# bldc_driver.net
KiCad netlist of a schematic drawn in EasyEDA Pro
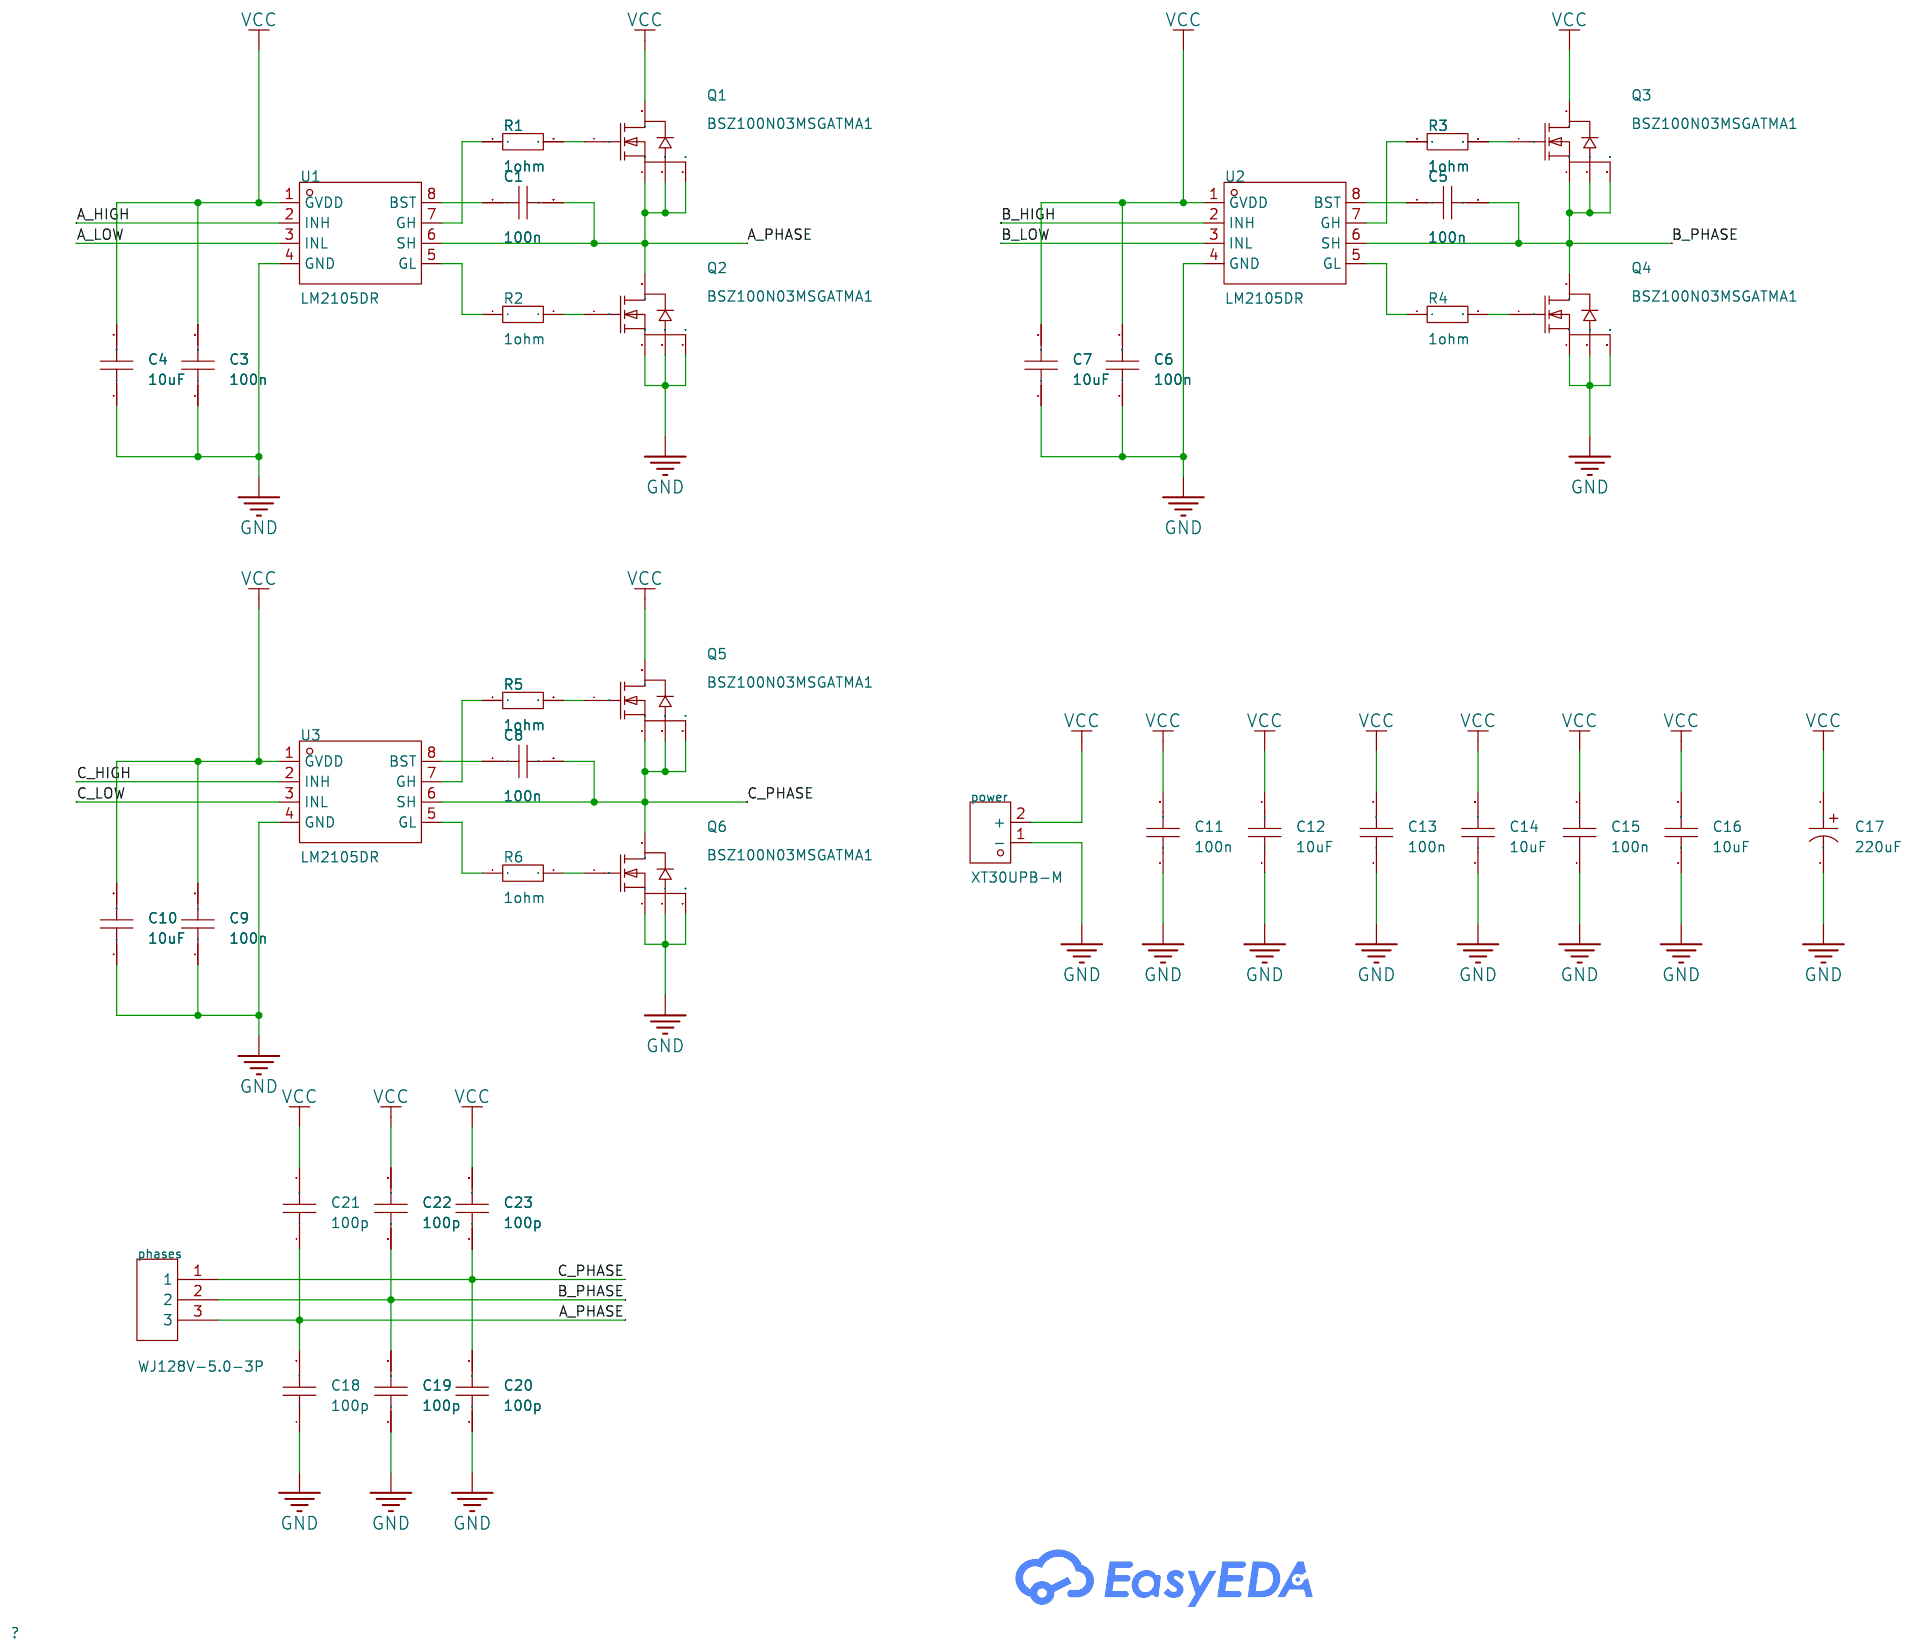
[diagram p0: power_drivers]
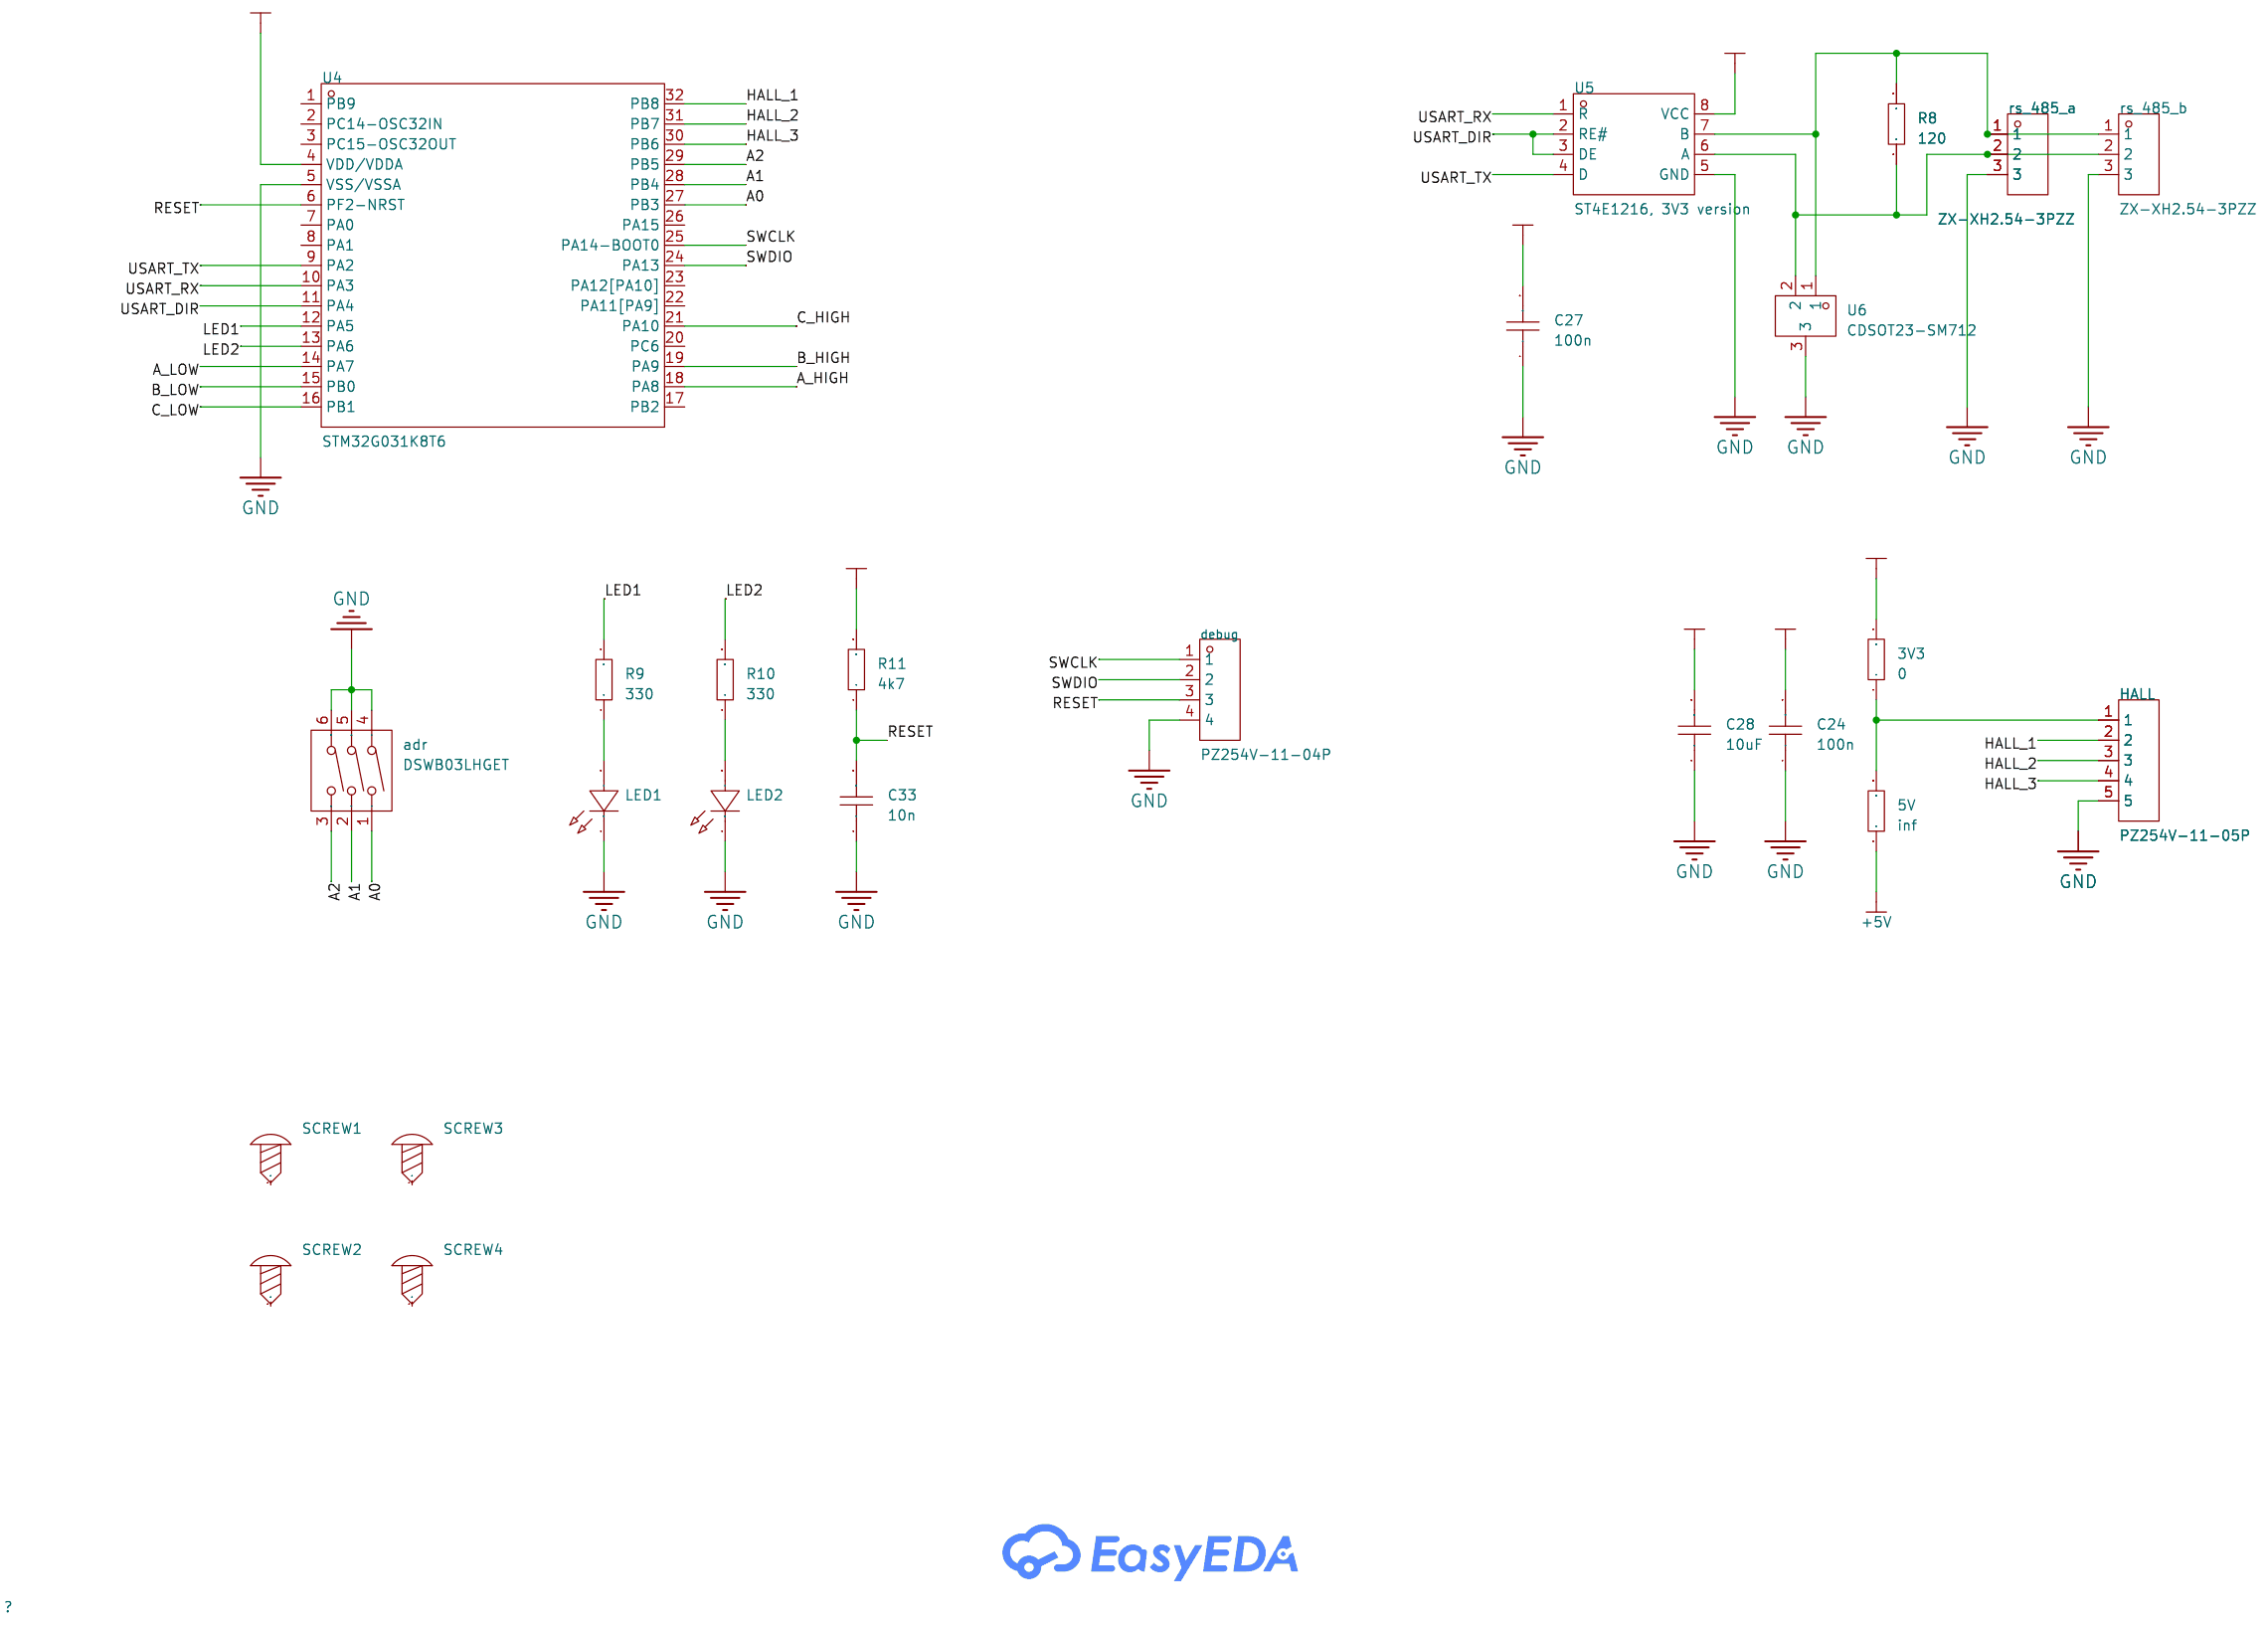
[diagram p1: main]
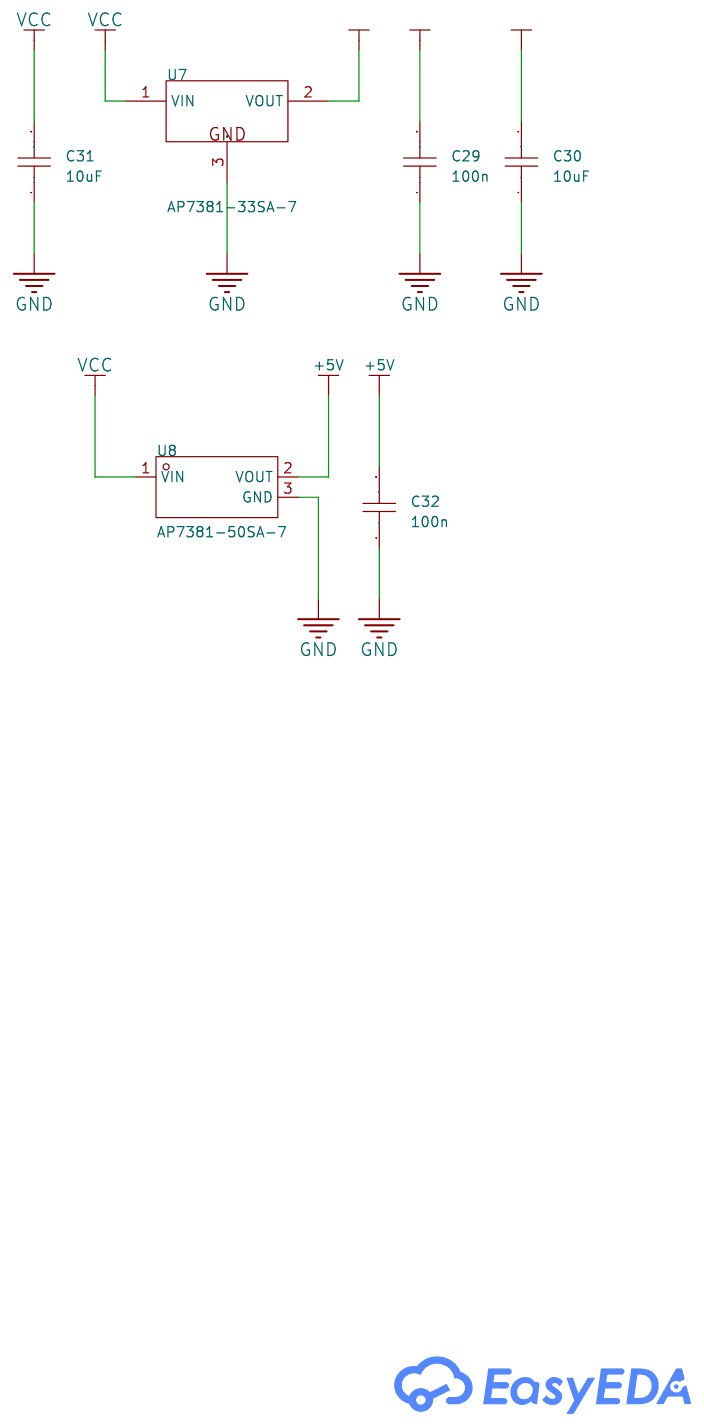
[diagram p2: supply]

(export (version "E")
  (design (tool "Eeschema 10.0.6"))
  (components
    (comp (ref "C1")
      (value "10uF")
      (footprint "easyedapro:C0805")
      (description "Capacitance:10uF Tolerance:±10% Tolerance:±10% Voltage Rating:25V Temperature Coefficient:X5R")
      (fields
        (field (name "Manufacturer Part") "CL21A106KAYNNNE")
        (field (name "Manufacturer") "SAMSUNG(三星)")
      )
      (libsource (lib "easyedapro") (part "CL21A106KAYNNNE"))
    )
    (comp (ref "C3")
      (value "10uF")
      (footprint "easyedapro:C0805")
      (description "Capacitance:10uF Tolerance:±10% Tolerance:±10% Voltage Rating:25V Temperature Coefficient:X5R")
      (fields
        (field (name "Manufacturer Part") "CL21A106KAYNNNE")
        (field (name "Manufacturer") "SAMSUNG(三星)")
      )
      (libsource (lib "easyedapro") (part "CL21A106KAYNNNE"))
    )
    (comp (ref "C4")
      (value "10uF")
      (footprint "easyedapro:C0805")
      (description "Capacitance:10uF Tolerance:±10% Tolerance:±10% Voltage Rating:25V Temperature Coefficient:X5R")
      (fields
        (field (name "Manufacturer Part") "CL21A106KAYNNNE")
        (field (name "Manufacturer") "SAMSUNG(三星)")
      )
      (libsource (lib "easyedapro") (part "CL21A106KAYNNNE"))
    )
    (comp (ref "C5")
      (value "10uF")
      (footprint "easyedapro:C0805")
      (description "Capacitance:10uF Tolerance:±10% Tolerance:±10% Voltage Rating:25V Temperature Coefficient:X5R")
      (fields
        (field (name "Manufacturer Part") "CL21A106KAYNNNE")
        (field (name "Manufacturer") "SAMSUNG(三星)")
      )
      (libsource (lib "easyedapro") (part "CL21A106KAYNNNE"))
    )
    (comp (ref "C6")
      (value "10uF")
      (footprint "easyedapro:C0805")
      (description "Capacitance:10uF Tolerance:±10% Tolerance:±10% Voltage Rating:25V Temperature Coefficient:X5R")
      (fields
        (field (name "Manufacturer Part") "CL21A106KAYNNNE")
        (field (name "Manufacturer") "SAMSUNG(三星)")
      )
      (libsource (lib "easyedapro") (part "CL21A106KAYNNNE"))
    )
    (comp (ref "C7")
      (value "10uF")
      (footprint "easyedapro:C0805")
      (description "Capacitance:10uF Tolerance:±10% Tolerance:±10% Voltage Rating:25V Temperature Coefficient:X5R")
      (fields
        (field (name "Manufacturer Part") "CL21A106KAYNNNE")
        (field (name "Manufacturer") "SAMSUNG(三星)")
      )
      (libsource (lib "easyedapro") (part "CL21A106KAYNNNE"))
    )
    (comp (ref "C8")
      (value "10uF")
      (footprint "easyedapro:C0805")
      (description "Capacitance:10uF Tolerance:±10% Tolerance:±10% Voltage Rating:25V Temperature Coefficient:X5R")
      (fields
        (field (name "Manufacturer Part") "CL21A106KAYNNNE")
        (field (name "Manufacturer") "SAMSUNG(三星)")
      )
      (libsource (lib "easyedapro") (part "CL21A106KAYNNNE"))
    )
    (comp (ref "C9")
      (value "10uF")
      (footprint "easyedapro:C0805")
      (description "Capacitance:10uF Tolerance:±10% Tolerance:±10% Voltage Rating:25V Temperature Coefficient:X5R")
      (fields
        (field (name "Manufacturer Part") "CL21A106KAYNNNE")
        (field (name "Manufacturer") "SAMSUNG(三星)")
      )
      (libsource (lib "easyedapro") (part "CL21A106KAYNNNE"))
    )
    (comp (ref "C10")
      (value "10uF")
      (footprint "easyedapro:C0805")
      (description "Capacitance:10uF Tolerance:±10% Tolerance:±10% Voltage Rating:25V Temperature Coefficient:X5R")
      (fields
        (field (name "Manufacturer Part") "CL21A106KAYNNNE")
        (field (name "Manufacturer") "SAMSUNG(三星)")
      )
      (libsource (lib "easyedapro") (part "CL21A106KAYNNNE"))
    )
    (comp (ref "C11")
      (value "10uF")
      (footprint "easyedapro:C0805")
      (description "Capacitance:10uF Tolerance:±10% Tolerance:±10% Voltage Rating:25V Temperature Coefficient:X5R")
      (fields
        (field (name "Manufacturer Part") "CL21A106KAYNNNE")
        (field (name "Manufacturer") "SAMSUNG(三星)")
      )
      (libsource (lib "easyedapro") (part "CL21A106KAYNNNE"))
    )
    (comp (ref "C12")
      (value "10uF")
      (footprint "easyedapro:C0805")
      (description "Capacitance:10uF Tolerance:±10% Tolerance:±10% Voltage Rating:25V Temperature Coefficient:X5R")
      (fields
        (field (name "Manufacturer Part") "CL21A106KAYNNNE")
        (field (name "Manufacturer") "SAMSUNG(三星)")
      )
      (libsource (lib "easyedapro") (part "CL21A106KAYNNNE"))
    )
    (comp (ref "C13")
      (value "10uF")
      (footprint "easyedapro:C0805")
      (description "Capacitance:10uF Tolerance:±10% Tolerance:±10% Voltage Rating:25V Temperature Coefficient:X5R")
      (fields
        (field (name "Manufacturer Part") "CL21A106KAYNNNE")
        (field (name "Manufacturer") "SAMSUNG(三星)")
      )
      (libsource (lib "easyedapro") (part "CL21A106KAYNNNE"))
    )
    (comp (ref "C14")
      (value "10uF")
      (footprint "easyedapro:C0805")
      (description "Capacitance:10uF Tolerance:±10% Tolerance:±10% Voltage Rating:25V Temperature Coefficient:X5R")
      (fields
        (field (name "Manufacturer Part") "CL21A106KAYNNNE")
        (field (name "Manufacturer") "SAMSUNG(三星)")
      )
      (libsource (lib "easyedapro") (part "CL21A106KAYNNNE"))
    )
    (comp (ref "C15")
      (value "10uF")
      (footprint "easyedapro:C0805")
      (description "Capacitance:10uF Tolerance:±10% Tolerance:±10% Voltage Rating:25V Temperature Coefficient:X5R")
      (fields
        (field (name "Manufacturer Part") "CL21A106KAYNNNE")
        (field (name "Manufacturer") "SAMSUNG(三星)")
      )
      (libsource (lib "easyedapro") (part "CL21A106KAYNNNE"))
    )
    (comp (ref "C16")
      (value "10uF")
      (footprint "easyedapro:C0805")
      (description "Capacitance:10uF Tolerance:±10% Tolerance:±10% Voltage Rating:25V Temperature Coefficient:X5R")
      (fields
        (field (name "Manufacturer Part") "CL21A106KAYNNNE")
        (field (name "Manufacturer") "SAMSUNG(三星)")
      )
      (libsource (lib "easyedapro") (part "CL21A106KAYNNNE"))
    )
    (comp (ref "C17")
      (value "220uF")
      (footprint "easyedapro:CAP-SMD_BD10.0-L10.3-W10.3-LS10.9-FD")
      (fields (field (name "Manufacturer Part") "XT1E221M1010") (field (name "Manufacturer") "JARSON(伽盛)"))
      (libsource (lib "easyedapro") (part "XT1E221M1010"))
    )
    (comp (ref "C18")
      (value "10uF")
      (footprint "easyedapro:C0805")
      (description "Capacitance:10uF Tolerance:±10% Tolerance:±10% Voltage Rating:25V Temperature Coefficient:X5R")
      (fields
        (field (name "Manufacturer Part") "CL21A106KAYNNNE")
        (field (name "Manufacturer") "SAMSUNG(三星)")
      )
      (libsource (lib "easyedapro") (part "CL21A106KAYNNNE"))
    )
    (comp (ref "C19")
      (value "10uF")
      (footprint "easyedapro:C0805")
      (description "Capacitance:10uF Tolerance:±10% Tolerance:±10% Voltage Rating:25V Temperature Coefficient:X5R")
      (fields
        (field (name "Manufacturer Part") "CL21A106KAYNNNE")
        (field (name "Manufacturer") "SAMSUNG(三星)")
      )
      (libsource (lib "easyedapro") (part "CL21A106KAYNNNE"))
    )
    (comp (ref "C20")
      (value "10uF")
      (footprint "easyedapro:C0805")
      (description "Capacitance:10uF Tolerance:±10% Tolerance:±10% Voltage Rating:25V Temperature Coefficient:X5R")
      (fields
        (field (name "Manufacturer Part") "CL21A106KAYNNNE")
        (field (name "Manufacturer") "SAMSUNG(三星)")
      )
      (libsource (lib "easyedapro") (part "CL21A106KAYNNNE"))
    )
    (comp (ref "C21")
      (value "10uF")
      (footprint "easyedapro:C0805")
      (description "Capacitance:10uF Tolerance:±10% Tolerance:±10% Voltage Rating:25V Temperature Coefficient:X5R")
      (fields
        (field (name "Manufacturer Part") "CL21A106KAYNNNE")
        (field (name "Manufacturer") "SAMSUNG(三星)")
      )
      (libsource (lib "easyedapro") (part "CL21A106KAYNNNE"))
    )
    (comp (ref "C22")
      (value "10uF")
      (footprint "easyedapro:C0805")
      (description "Capacitance:10uF Tolerance:±10% Tolerance:±10% Voltage Rating:25V Temperature Coefficient:X5R")
      (fields
        (field (name "Manufacturer Part") "CL21A106KAYNNNE")
        (field (name "Manufacturer") "SAMSUNG(三星)")
      )
      (libsource (lib "easyedapro") (part "CL21A106KAYNNNE"))
    )
    (comp (ref "C23")
      (value "10uF")
      (footprint "easyedapro:C0805")
      (description "Capacitance:10uF Tolerance:±10% Tolerance:±10% Voltage Rating:25V Temperature Coefficient:X5R")
      (fields
        (field (name "Manufacturer Part") "CL21A106KAYNNNE")
        (field (name "Manufacturer") "SAMSUNG(三星)")
      )
      (libsource (lib "easyedapro") (part "CL21A106KAYNNNE"))
    )
    (comp (ref "phases")
      (value "WJ128V-5.0-3P")
      (footprint "easyedapro:CONN-TH_3P-P5.00_WJ128V-5.0-3P")
      (fields (field (name "Manufacturer") "KANGNEX(康奈克斯电气)"))
      (libsource (lib "easyedapro") (part "WJ128V-5.0-3P"))
    )
    (comp (ref "power")
      (value "XT30UPB-M")
      (footprint "easyedapro:CONN-TH_XT30UPB-M")
      (fields (field (name "Manufacturer") "AMASS(艾迈斯)"))
      (libsource (lib "easyedapro") (part "XT30UPB-M"))
    )
    (comp (ref "Q1")
      (value "BSZ100N03MSGATMA1")
      (footprint "easyedapro:DFN-8_L3.3-W3.3-P0.65-BL-2")
      (fields (field (name "Manufacturer") "Infineon(英飞凌)"))
      (libsource (lib "easyedapro") (part "BSZ100N03MSGATMA1"))
    )
    (comp (ref "Q2")
      (value "BSZ100N03MSGATMA1")
      (footprint "easyedapro:DFN-8_L3.3-W3.3-P0.65-BL-2")
      (fields (field (name "Manufacturer") "Infineon(英飞凌)"))
      (libsource (lib "easyedapro") (part "BSZ100N03MSGATMA1"))
    )
    (comp (ref "Q3")
      (value "BSZ100N03MSGATMA1")
      (footprint "easyedapro:DFN-8_L3.3-W3.3-P0.65-BL-2")
      (fields (field (name "Manufacturer") "Infineon(英飞凌)"))
      (libsource (lib "easyedapro") (part "BSZ100N03MSGATMA1"))
    )
    (comp (ref "Q4")
      (value "BSZ100N03MSGATMA1")
      (footprint "easyedapro:DFN-8_L3.3-W3.3-P0.65-BL-2")
      (fields (field (name "Manufacturer") "Infineon(英飞凌)"))
      (libsource (lib "easyedapro") (part "BSZ100N03MSGATMA1"))
    )
    (comp (ref "Q5")
      (value "BSZ100N03MSGATMA1")
      (footprint "easyedapro:DFN-8_L3.3-W3.3-P0.65-BL-2")
      (fields (field (name "Manufacturer") "Infineon(英飞凌)"))
      (libsource (lib "easyedapro") (part "BSZ100N03MSGATMA1"))
    )
    (comp (ref "Q6")
      (value "BSZ100N03MSGATMA1")
      (footprint "easyedapro:DFN-8_L3.3-W3.3-P0.65-BL-2")
      (fields (field (name "Manufacturer") "Infineon(英飞凌)"))
      (libsource (lib "easyedapro") (part "BSZ100N03MSGATMA1"))
    )
    (comp (ref "R1")
      (value "10kΩ")
      (footprint "easyedapro:R0805")
      (fields
        (field (name "Manufacturer Part") "0805W8F1002T5E")
        (field (name "Manufacturer") "UNI-ROYAL(厚声)")
      )
      (libsource (lib "easyedapro") (part "0805W8F1002T5E"))
    )
    (comp (ref "R2")
      (value "10kΩ")
      (footprint "easyedapro:R0805")
      (fields
        (field (name "Manufacturer Part") "0805W8F1002T5E")
        (field (name "Manufacturer") "UNI-ROYAL(厚声)")
      )
      (libsource (lib "easyedapro") (part "0805W8F1002T5E"))
    )
    (comp (ref "R3")
      (value "10kΩ")
      (footprint "easyedapro:R0805")
      (fields
        (field (name "Manufacturer Part") "0805W8F1002T5E")
        (field (name "Manufacturer") "UNI-ROYAL(厚声)")
      )
      (libsource (lib "easyedapro") (part "0805W8F1002T5E"))
    )
    (comp (ref "R4")
      (value "10kΩ")
      (footprint "easyedapro:R0805")
      (fields
        (field (name "Manufacturer Part") "0805W8F1002T5E")
        (field (name "Manufacturer") "UNI-ROYAL(厚声)")
      )
      (libsource (lib "easyedapro") (part "0805W8F1002T5E"))
    )
    (comp (ref "R5")
      (value "10kΩ")
      (footprint "easyedapro:R0805")
      (fields
        (field (name "Manufacturer Part") "0805W8F1002T5E")
        (field (name "Manufacturer") "UNI-ROYAL(厚声)")
      )
      (libsource (lib "easyedapro") (part "0805W8F1002T5E"))
    )
    (comp (ref "R6")
      (value "10kΩ")
      (footprint "easyedapro:R0805")
      (fields
        (field (name "Manufacturer Part") "0805W8F1002T5E")
        (field (name "Manufacturer") "UNI-ROYAL(厚声)")
      )
      (libsource (lib "easyedapro") (part "0805W8F1002T5E"))
    )
    (comp (ref "U1")
      (value "LM2105DR")
      (footprint "easyedapro:SOIC-8_L4.9-W3.9-P1.27-LS6.0-BL")
      (fields (field (name "Manufacturer") "TI(德州仪器)"))
      (libsource (lib "easyedapro") (part "LM2105DR"))
    )
    (comp (ref "U2")
      (value "LM2105DR")
      (footprint "easyedapro:SOIC-8_L4.9-W3.9-P1.27-LS6.0-BL")
      (fields (field (name "Manufacturer") "TI(德州仪器)"))
      (libsource (lib "easyedapro") (part "LM2105DR"))
    )
    (comp (ref "U3")
      (value "LM2105DR")
      (footprint "easyedapro:SOIC-8_L4.9-W3.9-P1.27-LS6.0-BL")
      (fields (field (name "Manufacturer") "TI(德州仪器)"))
      (libsource (lib "easyedapro") (part "LM2105DR"))
    )
    (comp (ref "3V3")
      (value "10kΩ")
      (footprint "easyedapro:R0805")
      (fields
        (field (name "Manufacturer Part") "0805W8F1002T5E")
        (field (name "Manufacturer") "UNI-ROYAL(厚声)")
      )
      (libsource (lib "easyedapro") (part "0805W8F1002T5E"))
    )
    (comp (ref "5V")
      (value "10kΩ")
      (footprint "easyedapro:R0805")
      (fields
        (field (name "Manufacturer Part") "0805W8F1002T5E")
        (field (name "Manufacturer") "UNI-ROYAL(厚声)")
      )
      (libsource (lib "easyedapro") (part "0805W8F1002T5E"))
    )
    (comp (ref "adr")
      (value "DSWB03LHGET")
      (footprint "easyedapro:SW-TH_DSWB03LHGET")
      (description "Type:Slide, Rocked Circuit:SPST Number of Positions:3 Lead Pitch:2.54mm Operating Life:- Color:Red")
      (fields (field (name "Manufacturer") "YE"))
      (libsource (lib "easyedapro") (part "DSWB03LHGET"))
    )
    (comp (ref "C24")
      (value "10uF")
      (footprint "easyedapro:C0805")
      (description "Capacitance:10uF Tolerance:±10% Tolerance:±10% Voltage Rating:25V Temperature Coefficient:X5R")
      (fields
        (field (name "Manufacturer Part") "CL21A106KAYNNNE")
        (field (name "Manufacturer") "SAMSUNG(三星)")
      )
      (libsource (lib "easyedapro") (part "CL21A106KAYNNNE"))
    )
    (comp (ref "C27")
      (value "10uF")
      (footprint "easyedapro:C0805")
      (description "Capacitance:10uF Tolerance:±10% Tolerance:±10% Voltage Rating:25V Temperature Coefficient:X5R")
      (fields
        (field (name "Manufacturer Part") "CL21A106KAYNNNE")
        (field (name "Manufacturer") "SAMSUNG(三星)")
      )
      (libsource (lib "easyedapro") (part "CL21A106KAYNNNE"))
    )
    (comp (ref "C28")
      (value "10uF")
      (footprint "easyedapro:C0805")
      (description "Capacitance:10uF Tolerance:±10% Tolerance:±10% Voltage Rating:25V Temperature Coefficient:X5R")
      (fields
        (field (name "Manufacturer Part") "CL21A106KAYNNNE")
        (field (name "Manufacturer") "SAMSUNG(三星)")
      )
      (libsource (lib "easyedapro") (part "CL21A106KAYNNNE"))
    )
    (comp (ref "C33")
      (value "10uF")
      (footprint "easyedapro:C0805")
      (description "Capacitance:10uF Tolerance:±10% Tolerance:±10% Voltage Rating:25V Temperature Coefficient:X5R")
      (fields
        (field (name "Manufacturer Part") "CL21A106KAYNNNE")
        (field (name "Manufacturer") "SAMSUNG(三星)")
      )
      (libsource (lib "easyedapro") (part "CL21A106KAYNNNE"))
    )
    (comp (ref "debug")
      (value "PZ254V-11-04P")
      (footprint "easyedapro:HDR-TH_4P-P2.54-V-M")
      (fields (field (name "Manufacturer") "XFCN(兴飞)"))
      (libsource (lib "easyedapro") (part "PZ254V-11-04P_C2691448"))
    )
    (comp (ref "HALL")
      (value "PZ254V-11-05P")
      (footprint "easyedapro:HDR-TH_5P-P2.54-V-M")
      (fields (field (name "Manufacturer") "XFCN(兴飞)"))
      (libsource (lib "easyedapro") (part "PZ254V-11-05P"))
    )
    (comp (ref "LED1")
      (value "P2-1206RTCS2-0.9T-F")
      (footprint "easyedapro:LED-SMD_L3.2-W1.6-P2-1206RTCS2-0.9T-F")
      (fields (field (name "Manufacturer") "TUOZHAN(拓展光电)"))
      (libsource (lib "easyedapro") (part "P2-1206RTCS2-0.9T-F"))
    )
    (comp (ref "LED2")
      (value "P2-1206RTCS2-0.9T-F")
      (footprint "easyedapro:LED-SMD_L3.2-W1.6-P2-1206RTCS2-0.9T-F")
      (fields (field (name "Manufacturer") "TUOZHAN(拓展光电)"))
      (libsource (lib "easyedapro") (part "P2-1206RTCS2-0.9T-F"))
    )
    (comp (ref "R8")
      (value "10kΩ")
      (footprint "easyedapro:R0805")
      (fields
        (field (name "Manufacturer Part") "0805W8F1002T5E")
        (field (name "Manufacturer") "UNI-ROYAL(厚声)")
      )
      (libsource (lib "easyedapro") (part "0805W8F1002T5E"))
    )
    (comp (ref "R9")
      (value "10kΩ")
      (footprint "easyedapro:R0805")
      (fields
        (field (name "Manufacturer Part") "0805W8F1002T5E")
        (field (name "Manufacturer") "UNI-ROYAL(厚声)")
      )
      (libsource (lib "easyedapro") (part "0805W8F1002T5E"))
    )
    (comp (ref "R10")
      (value "10kΩ")
      (footprint "easyedapro:R0805")
      (fields
        (field (name "Manufacturer Part") "0805W8F1002T5E")
        (field (name "Manufacturer") "UNI-ROYAL(厚声)")
      )
      (libsource (lib "easyedapro") (part "0805W8F1002T5E"))
    )
    (comp (ref "R11")
      (value "10kΩ")
      (footprint "easyedapro:R0805")
      (fields
        (field (name "Manufacturer Part") "0805W8F1002T5E")
        (field (name "Manufacturer") "UNI-ROYAL(厚声)")
      )
      (libsource (lib "easyedapro") (part "0805W8F1002T5E"))
    )
    (comp (ref "rs_485_a")
      (value "ZX-XH2.54-3PZZ")
      (footprint "easyedapro:CONN-TH_3P-P2.54_2501S-3P")
      (fields (field (name "Manufacturer") "Megastar(兆星)"))
      (libsource (lib "easyedapro") (part "ZX-XH2.54-3PZZ"))
    )
    (comp (ref "rs_485_b")
      (value "ZX-XH2.54-3PZZ")
      (footprint "easyedapro:CONN-TH_3P-P2.54_2501S-3P")
      (fields (field (name "Manufacturer") "Megastar(兆星)"))
      (libsource (lib "easyedapro") (part "ZX-XH2.54-3PZZ"))
    )
    (comp (ref "SCREW1")
      (value "~")
      (footprint "easyedapro:Screw-Hole-M3")
      (libsource (lib "easyedapro") (part "Screw-Hole"))
    )
    (comp (ref "SCREW2")
      (value "~")
      (footprint "easyedapro:Screw-Hole-M3")
      (libsource (lib "easyedapro") (part "Screw-Hole"))
    )
    (comp (ref "SCREW3")
      (value "~")
      (footprint "easyedapro:Screw-Hole-M3")
      (libsource (lib "easyedapro") (part "Screw-Hole"))
    )
    (comp (ref "SCREW4")
      (value "~")
      (footprint "easyedapro:Screw-Hole-M3")
      (libsource (lib "easyedapro") (part "Screw-Hole"))
    )
    (comp (ref "U4")
      (value "STM32G031K8T6")
      (footprint "easyedapro:LQFP-32_L7.0-W7.0-P0.80-LS9.0-BL")
      (fields (field (name "Manufacturer") "ST(意法半导体)"))
      (libsource (lib "easyedapro") (part "STM32G031K8T6"))
    )
    (comp (ref "U5")
      (value "ST4E1216, 3V3 version")
      (footprint "easyedapro:NSOIC-8_L4.9-W3.9-P1.27-LS6.1-BL")
      (fields (field (name "Manufacturer") "TI(德州仪器)"))
      (libsource (lib "easyedapro") (part "THVD1510DR"))
    )
    (comp (ref "U6")
      (value "CDSOT23-SM712")
      (footprint "easyedapro:SOT-23-3_L2.9-W1.3-P0.95-LS2.4-BR")
      (fields (field (name "Manufacturer") "TECH PUBLIC(台舟)"))
      (libsource (lib "easyedapro") (part "CDSOT23-SM712_C5122012"))
    )
    (comp (ref "C29")
      (value "10uF")
      (footprint "easyedapro:C0805")
      (description "Capacitance:10uF Tolerance:±10% Tolerance:±10% Voltage Rating:25V Temperature Coefficient:X5R")
      (fields
        (field (name "Manufacturer Part") "CL21A106KAYNNNE")
        (field (name "Manufacturer") "SAMSUNG(三星)")
      )
      (libsource (lib "easyedapro") (part "CL21A106KAYNNNE"))
    )
    (comp (ref "C30")
      (value "10uF")
      (footprint "easyedapro:C0805")
      (description "Capacitance:10uF Tolerance:±10% Tolerance:±10% Voltage Rating:25V Temperature Coefficient:X5R")
      (fields
        (field (name "Manufacturer Part") "CL21A106KAYNNNE")
        (field (name "Manufacturer") "SAMSUNG(三星)")
      )
      (libsource (lib "easyedapro") (part "CL21A106KAYNNNE"))
    )
    (comp (ref "C31")
      (value "10uF")
      (footprint "easyedapro:C0805")
      (description "Capacitance:10uF Tolerance:±10% Tolerance:±10% Voltage Rating:25V Temperature Coefficient:X5R")
      (fields
        (field (name "Manufacturer Part") "CL21A106KAYNNNE")
        (field (name "Manufacturer") "SAMSUNG(三星)")
      )
      (libsource (lib "easyedapro") (part "CL21A106KAYNNNE"))
    )
    (comp (ref "C32")
      (value "10uF")
      (footprint "easyedapro:C0805")
      (description "Capacitance:10uF Tolerance:±10% Tolerance:±10% Voltage Rating:25V Temperature Coefficient:X5R")
      (fields
        (field (name "Manufacturer Part") "CL21A106KAYNNNE")
        (field (name "Manufacturer") "SAMSUNG(三星)")
      )
      (libsource (lib "easyedapro") (part "CL21A106KAYNNNE"))
    )
    (comp (ref "U7")
      (value "AP7381-33SA-7")
      (footprint "easyedapro:SOT-23-3_L2.9-W1.3-P1.90-LS2.4-BR")
      (fields (field (name "Manufacturer") "DIODES(美台)"))
      (libsource (lib "easyedapro") (part "AP7381-33SA-7"))
    )
    (comp (ref "U8")
      (value "AP7381-50SA-7")
      (footprint "easyedapro:SOT-23-3_L2.9-W1.5-P1.90-LS2.6-BR")
      (fields (field (name "Manufacturer") "DIODES(美台)"))
      (libsource (lib "easyedapro") (part "AP7381-50SA-7"))
    )
  )
  (nets
    (net (code "1") (name "+3V3") (class "Default")
      (node (ref "3V3") (pin "2") (pinfunction "2_2") (pintype "input"))
      (node (ref "C24") (pin "2") (pinfunction "2_2") (pintype "unspecified"))
      (node (ref "C27") (pin "2") (pinfunction "2_2") (pintype "unspecified"))
      (node (ref "C28") (pin "2") (pinfunction "2_2") (pintype "unspecified"))
      (node (ref "C29") (pin "2") (pinfunction "2_2") (pintype "unspecified"))
      (node (ref "C30") (pin "2") (pinfunction "2_2") (pintype "unspecified"))
      (node (ref "R11") (pin "2") (pinfunction "2_2") (pintype "input"))
      (node (ref "U4") (pin "4") (pinfunction "VDD/VDDA_4") (pintype "unspecified"))
      (node (ref "U5") (pin "8") (pinfunction "VCC_8") (pintype "unspecified"))
      (node (ref "U7") (pin "2") (pinfunction "VOUT_2") (pintype "unspecified"))
    )
    (net (code "2") (name "+5V") (class "Default")
      (node (ref "5V") (pin "1") (pinfunction "1_1") (pintype "input"))
      (node (ref "C32") (pin "2") (pinfunction "2_2") (pintype "unspecified"))
      (node (ref "U8") (pin "2") (pinfunction "VOUT_2") (pintype "unspecified"))
    )
    (net (code "3") (name "A0") (class "Default")
      (node (ref "U4") (pin "27") (pinfunction "PB3_27") (pintype "unspecified"))
      (node (ref "adr") (pin "1") (pinfunction "1_1") (pintype "unspecified"))
    )
    (net (code "4") (name "A1") (class "Default")
      (node (ref "U4") (pin "28") (pinfunction "PB4_28") (pintype "unspecified"))
      (node (ref "adr") (pin "2") (pinfunction "2_2") (pintype "unspecified"))
    )
    (net (code "5") (name "A2") (class "Default")
      (node (ref "U4") (pin "29") (pinfunction "PB5_29") (pintype "unspecified"))
      (node (ref "adr") (pin "3") (pinfunction "3_3") (pintype "unspecified"))
    )
    (net (code "6") (name "A_HIGH") (class "Default")
      (node (ref "U1") (pin "2") (pinfunction "INH_2") (pintype "unspecified"))
      (node (ref "U4") (pin "18") (pinfunction "PA8_18") (pintype "unspecified"))
    )
    (net (code "7") (name "A_LOW") (class "Default")
      (node (ref "U1") (pin "3") (pinfunction "INL_3") (pintype "unspecified"))
      (node (ref "U4") (pin "14") (pinfunction "PA7_14") (pintype "unspecified"))
    )
    (net (code "8") (name "A_PHASE") (class "Default")
      (node (ref "C1") (pin "2") (pinfunction "2_2") (pintype "unspecified"))
      (node (ref "C18") (pin "2") (pinfunction "2_2") (pintype "unspecified"))
      (node (ref "C21") (pin "1") (pinfunction "1_1") (pintype "unspecified"))
      (node (ref "Q1") (pin "1") (pinfunction "S_1") (pintype "unspecified"))
      (node (ref "Q1") (pin "2") (pinfunction "S_2") (pintype "unspecified"))
      (node (ref "Q1") (pin "3") (pinfunction "S_3") (pintype "unspecified"))
      (node (ref "Q2") (pin "5") (pinfunction "D_5") (pintype "unspecified"))
      (node (ref "U1") (pin "6") (pinfunction "SH_6") (pintype "unspecified"))
      (node (ref "phases") (pin "3") (pinfunction "3_3") (pintype "input"))
    )
    (net (code "9") (name "B_HIGH") (class "Default")
      (node (ref "U2") (pin "2") (pinfunction "INH_2") (pintype "unspecified"))
      (node (ref "U4") (pin "19") (pinfunction "PA9_19") (pintype "unspecified"))
    )
    (net (code "10") (name "B_LOW") (class "Default")
      (node (ref "U2") (pin "3") (pinfunction "INL_3") (pintype "unspecified"))
      (node (ref "U4") (pin "15") (pinfunction "PB0_15") (pintype "unspecified"))
    )
    (net (code "11") (name "B_PHASE") (class "Default")
      (node (ref "C19") (pin "2") (pinfunction "2_2") (pintype "unspecified"))
      (node (ref "C22") (pin "1") (pinfunction "1_1") (pintype "unspecified"))
      (node (ref "C5") (pin "2") (pinfunction "2_2") (pintype "unspecified"))
      (node (ref "Q3") (pin "1") (pinfunction "S_1") (pintype "unspecified"))
      (node (ref "Q3") (pin "2") (pinfunction "S_2") (pintype "unspecified"))
      (node (ref "Q3") (pin "3") (pinfunction "S_3") (pintype "unspecified"))
      (node (ref "Q4") (pin "5") (pinfunction "D_5") (pintype "unspecified"))
      (node (ref "U2") (pin "6") (pinfunction "SH_6") (pintype "unspecified"))
      (node (ref "phases") (pin "2") (pinfunction "2_2") (pintype "input"))
    )
    (net (code "12") (name "C_HIGH") (class "Default")
      (node (ref "U3") (pin "2") (pinfunction "INH_2") (pintype "unspecified"))
      (node (ref "U4") (pin "21") (pinfunction "PA10_21") (pintype "unspecified"))
    )
    (net (code "13") (name "C_LOW") (class "Default")
      (node (ref "U3") (pin "3") (pinfunction "INL_3") (pintype "unspecified"))
      (node (ref "U4") (pin "16") (pinfunction "PB1_16") (pintype "unspecified"))
    )
    (net (code "14") (name "C_PHASE") (class "Default")
      (node (ref "C20") (pin "2") (pinfunction "2_2") (pintype "unspecified"))
      (node (ref "C23") (pin "1") (pinfunction "1_1") (pintype "unspecified"))
      (node (ref "C8") (pin "2") (pinfunction "2_2") (pintype "unspecified"))
      (node (ref "Q5") (pin "1") (pinfunction "S_1") (pintype "unspecified"))
      (node (ref "Q5") (pin "2") (pinfunction "S_2") (pintype "unspecified"))
      (node (ref "Q5") (pin "3") (pinfunction "S_3") (pintype "unspecified"))
      (node (ref "Q6") (pin "5") (pinfunction "D_5") (pintype "unspecified"))
      (node (ref "U3") (pin "6") (pinfunction "SH_6") (pintype "unspecified"))
      (node (ref "phases") (pin "1") (pinfunction "1_1") (pintype "input"))
    )
    (net (code "15") (name "GND") (class "Default")
      (node (ref "C10") (pin "1") (pinfunction "1_1") (pintype "unspecified"))
      (node (ref "C11") (pin "1") (pinfunction "1_1") (pintype "unspecified"))
      (node (ref "C12") (pin "1") (pinfunction "1_1") (pintype "unspecified"))
      (node (ref "C13") (pin "1") (pinfunction "1_1") (pintype "unspecified"))
      (node (ref "C14") (pin "1") (pinfunction "1_1") (pintype "unspecified"))
      (node (ref "C15") (pin "1") (pinfunction "1_1") (pintype "unspecified"))
      (node (ref "C16") (pin "1") (pinfunction "1_1") (pintype "unspecified"))
      (node (ref "C17") (pin "2") (pinfunction "2_2") (pintype "input"))
      (node (ref "C18") (pin "1") (pinfunction "1_1") (pintype "unspecified"))
      (node (ref "C19") (pin "1") (pinfunction "1_1") (pintype "unspecified"))
      (node (ref "C20") (pin "1") (pinfunction "1_1") (pintype "unspecified"))
      (node (ref "C24") (pin "1") (pinfunction "1_1") (pintype "unspecified"))
      (node (ref "C27") (pin "1") (pinfunction "1_1") (pintype "unspecified"))
      (node (ref "C28") (pin "1") (pinfunction "1_1") (pintype "unspecified"))
      (node (ref "C29") (pin "1") (pinfunction "1_1") (pintype "unspecified"))
      (node (ref "C3") (pin "1") (pinfunction "1_1") (pintype "unspecified"))
      (node (ref "C30") (pin "1") (pinfunction "1_1") (pintype "unspecified"))
      (node (ref "C31") (pin "1") (pinfunction "1_1") (pintype "unspecified"))
      (node (ref "C32") (pin "1") (pinfunction "1_1") (pintype "unspecified"))
      (node (ref "C33") (pin "1") (pinfunction "1_1") (pintype "unspecified"))
      (node (ref "C4") (pin "1") (pinfunction "1_1") (pintype "unspecified"))
      (node (ref "C6") (pin "1") (pinfunction "1_1") (pintype "unspecified"))
      (node (ref "C7") (pin "1") (pinfunction "1_1") (pintype "unspecified"))
      (node (ref "C9") (pin "1") (pinfunction "1_1") (pintype "unspecified"))
      (node (ref "HALL") (pin "5") (pinfunction "5_5") (pintype "unspecified"))
      (node (ref "LED1") (pin "1") (pinfunction "C_1") (pintype "unspecified"))
      (node (ref "LED2") (pin "1") (pinfunction "C_1") (pintype "unspecified"))
      (node (ref "Q2") (pin "1") (pinfunction "S_1") (pintype "unspecified"))
      (node (ref "Q2") (pin "2") (pinfunction "S_2") (pintype "unspecified"))
      (node (ref "Q2") (pin "3") (pinfunction "S_3") (pintype "unspecified"))
      (node (ref "Q4") (pin "1") (pinfunction "S_1") (pintype "unspecified"))
      (node (ref "Q4") (pin "2") (pinfunction "S_2") (pintype "unspecified"))
      (node (ref "Q4") (pin "3") (pinfunction "S_3") (pintype "unspecified"))
      (node (ref "Q6") (pin "1") (pinfunction "S_1") (pintype "unspecified"))
      (node (ref "Q6") (pin "2") (pinfunction "S_2") (pintype "unspecified"))
      (node (ref "Q6") (pin "3") (pinfunction "S_3") (pintype "unspecified"))
      (node (ref "U1") (pin "4") (pinfunction "GND_4") (pintype "unspecified"))
      (node (ref "U2") (pin "4") (pinfunction "GND_4") (pintype "unspecified"))
      (node (ref "U3") (pin "4") (pinfunction "GND_4") (pintype "unspecified"))
      (node (ref "U4") (pin "5") (pinfunction "VSS/VSSA_5") (pintype "unspecified"))
      (node (ref "U5") (pin "5") (pinfunction "GND_5") (pintype "unspecified"))
      (node (ref "U6") (pin "3") (pinfunction "3_3") (pintype "unspecified"))
      (node (ref "U7") (pin "3") (pinfunction "GND_3") (pintype "unspecified"))
      (node (ref "U8") (pin "3") (pinfunction "GND_3") (pintype "unspecified"))
      (node (ref "adr") (pin "4") (pinfunction "4_4") (pintype "unspecified"))
      (node (ref "adr") (pin "5") (pinfunction "5_5") (pintype "unspecified"))
      (node (ref "adr") (pin "6") (pinfunction "6_6") (pintype "unspecified"))
      (node (ref "debug") (pin "4") (pinfunction "4_4") (pintype "input"))
      (node (ref "power") (pin "1") (pinfunction "-_1") (pintype "input"))
      (node (ref "rs_485_a") (pin "3") (pinfunction "3_3") (pintype "unspecified"))
      (node (ref "rs_485_b") (pin "3") (pinfunction "3_3") (pintype "unspecified"))
    )
    (net (code "16") (name "HALL_1") (class "Default")
      (node (ref "HALL") (pin "2") (pinfunction "2_2") (pintype "unspecified"))
      (node (ref "U4") (pin "32") (pinfunction "PB8_32") (pintype "unspecified"))
    )
    (net (code "17") (name "HALL_2") (class "Default")
      (node (ref "HALL") (pin "3") (pinfunction "3_3") (pintype "unspecified"))
      (node (ref "U4") (pin "31") (pinfunction "PB7_31") (pintype "unspecified"))
    )
    (net (code "18") (name "HALL_3") (class "Default")
      (node (ref "HALL") (pin "4") (pinfunction "4_4") (pintype "unspecified"))
      (node (ref "U4") (pin "30") (pinfunction "PB6_30") (pintype "unspecified"))
    )
    (net (code "19") (name "LED1") (class "Default")
      (node (ref "R9") (pin "2") (pinfunction "2_2") (pintype "input"))
      (node (ref "U4") (pin "12") (pinfunction "PA5_12") (pintype "unspecified"))
    )
    (net (code "20") (name "LED2") (class "Default")
      (node (ref "R10") (pin "2") (pinfunction "2_2") (pintype "input"))
      (node (ref "U4") (pin "13") (pinfunction "PA6_13") (pintype "unspecified"))
    )
    (net (code "21") (name "Net-(3V3-Pad1)") (class "Default")
      (node (ref "3V3") (pin "1") (pinfunction "1_1") (pintype "input"))
      (node (ref "5V") (pin "2") (pinfunction "2_2") (pintype "input"))
      (node (ref "HALL") (pin "1") (pinfunction "1_1") (pintype "unspecified"))
    )
    (net (code "22") (name "Net-(LED1-A)") (class "Default")
      (node (ref "LED1") (pin "2") (pinfunction "A_2") (pintype "unspecified"))
      (node (ref "R9") (pin "1") (pinfunction "1_1") (pintype "input"))
    )
    (net (code "23") (name "Net-(LED2-A)") (class "Default")
      (node (ref "LED2") (pin "2") (pinfunction "A_2") (pintype "unspecified"))
      (node (ref "R10") (pin "1") (pinfunction "1_1") (pintype "input"))
    )
    (net (code "24") (name "Net-(Q1-G)") (class "Default")
      (node (ref "Q1") (pin "4") (pinfunction "G_4") (pintype "unspecified"))
      (node (ref "R1") (pin "2") (pinfunction "2_2") (pintype "input"))
    )
    (net (code "25") (name "Net-(Q2-G)") (class "Default")
      (node (ref "Q2") (pin "4") (pinfunction "G_4") (pintype "unspecified"))
      (node (ref "R2") (pin "2") (pinfunction "2_2") (pintype "input"))
    )
    (net (code "26") (name "Net-(Q3-G)") (class "Default")
      (node (ref "Q3") (pin "4") (pinfunction "G_4") (pintype "unspecified"))
      (node (ref "R3") (pin "2") (pinfunction "2_2") (pintype "input"))
    )
    (net (code "27") (name "Net-(Q4-G)") (class "Default")
      (node (ref "Q4") (pin "4") (pinfunction "G_4") (pintype "unspecified"))
      (node (ref "R4") (pin "2") (pinfunction "2_2") (pintype "input"))
    )
    (net (code "28") (name "Net-(Q5-G)") (class "Default")
      (node (ref "Q5") (pin "4") (pinfunction "G_4") (pintype "unspecified"))
      (node (ref "R5") (pin "2") (pinfunction "2_2") (pintype "input"))
    )
    (net (code "29") (name "Net-(Q6-G)") (class "Default")
      (node (ref "Q6") (pin "4") (pinfunction "G_4") (pintype "unspecified"))
      (node (ref "R6") (pin "2") (pinfunction "2_2") (pintype "input"))
    )
    (net (code "30") (name "Net-(U1-BST)") (class "Default")
      (node (ref "C1") (pin "1") (pinfunction "1_1") (pintype "unspecified"))
      (node (ref "U1") (pin "8") (pinfunction "BST_8") (pintype "unspecified"))
    )
    (net (code "31") (name "Net-(U1-GH)") (class "Default")
      (node (ref "R1") (pin "1") (pinfunction "1_1") (pintype "input"))
      (node (ref "U1") (pin "7") (pinfunction "GH_7") (pintype "unspecified"))
    )
    (net (code "32") (name "Net-(U1-GL)") (class "Default")
      (node (ref "R2") (pin "1") (pinfunction "1_1") (pintype "input"))
      (node (ref "U1") (pin "5") (pinfunction "GL_5") (pintype "unspecified"))
    )
    (net (code "33") (name "Net-(U2-BST)") (class "Default")
      (node (ref "C5") (pin "1") (pinfunction "1_1") (pintype "unspecified"))
      (node (ref "U2") (pin "8") (pinfunction "BST_8") (pintype "unspecified"))
    )
    (net (code "34") (name "Net-(U2-GH)") (class "Default")
      (node (ref "R3") (pin "1") (pinfunction "1_1") (pintype "input"))
      (node (ref "U2") (pin "7") (pinfunction "GH_7") (pintype "unspecified"))
    )
    (net (code "35") (name "Net-(U2-GL)") (class "Default")
      (node (ref "R4") (pin "1") (pinfunction "1_1") (pintype "input"))
      (node (ref "U2") (pin "5") (pinfunction "GL_5") (pintype "unspecified"))
    )
    (net (code "36") (name "Net-(U3-BST)") (class "Default")
      (node (ref "C8") (pin "1") (pinfunction "1_1") (pintype "unspecified"))
      (node (ref "U3") (pin "8") (pinfunction "BST_8") (pintype "unspecified"))
    )
    (net (code "37") (name "Net-(U3-GH)") (class "Default")
      (node (ref "R5") (pin "1") (pinfunction "1_1") (pintype "input"))
      (node (ref "U3") (pin "7") (pinfunction "GH_7") (pintype "unspecified"))
    )
    (net (code "38") (name "Net-(U3-GL)") (class "Default")
      (node (ref "R6") (pin "1") (pinfunction "1_1") (pintype "input"))
      (node (ref "U3") (pin "5") (pinfunction "GL_5") (pintype "unspecified"))
    )
    (net (code "39") (name "Net-(U5-A)") (class "Default")
      (node (ref "R8") (pin "1") (pinfunction "1_1") (pintype "input"))
      (node (ref "U5") (pin "6") (pinfunction "A_6") (pintype "unspecified"))
      (node (ref "U6") (pin "2") (pinfunction "2_2") (pintype "unspecified"))
      (node (ref "rs_485_a") (pin "2") (pinfunction "2_2") (pintype "unspecified"))
      (node (ref "rs_485_b") (pin "2") (pinfunction "2_2") (pintype "unspecified"))
    )
    (net (code "40") (name "Net-(U5-B)") (class "Default")
      (node (ref "R8") (pin "2") (pinfunction "2_2") (pintype "input"))
      (node (ref "U5") (pin "7") (pinfunction "B_7") (pintype "unspecified"))
      (node (ref "U6") (pin "1") (pinfunction "1_1") (pintype "unspecified"))
      (node (ref "rs_485_a") (pin "1") (pinfunction "1_1") (pintype "unspecified"))
      (node (ref "rs_485_b") (pin "1") (pinfunction "1_1") (pintype "unspecified"))
    )
    (net (code "41") (name "RESET") (class "Default")
      (node (ref "C33") (pin "2") (pinfunction "2_2") (pintype "unspecified"))
      (node (ref "R11") (pin "1") (pinfunction "1_1") (pintype "input"))
      (node (ref "U4") (pin "6") (pinfunction "PF2-NRST_6") (pintype "unspecified"))
      (node (ref "debug") (pin "3") (pinfunction "3_3") (pintype "input"))
    )
    (net (code "42") (name "SWCLK") (class "Default")
      (node (ref "U4") (pin "25") (pinfunction "PA14-BOOT0_25") (pintype "unspecified"))
      (node (ref "debug") (pin "1") (pinfunction "1_1") (pintype "input"))
    )
    (net (code "43") (name "SWDIO") (class "Default")
      (node (ref "U4") (pin "24") (pinfunction "PA13_24") (pintype "unspecified"))
      (node (ref "debug") (pin "2") (pinfunction "2_2") (pintype "input"))
    )
    (net (code "44") (name "USART_DIR") (class "Default")
      (node (ref "U4") (pin "11") (pinfunction "PA4_11") (pintype "unspecified"))
      (node (ref "U5") (pin "2") (pinfunction "RE#_2") (pintype "unspecified"))
      (node (ref "U5") (pin "3") (pinfunction "DE_3") (pintype "unspecified"))
    )
    (net (code "45") (name "USART_RX") (class "Default")
      (node (ref "U4") (pin "10") (pinfunction "PA3_10") (pintype "unspecified"))
      (node (ref "U5") (pin "1") (pinfunction "R_1") (pintype "unspecified"))
    )
    (net (code "46") (name "USART_TX") (class "Default")
      (node (ref "U4") (pin "9") (pinfunction "PA2_9") (pintype "unspecified"))
      (node (ref "U5") (pin "4") (pinfunction "D_4") (pintype "unspecified"))
    )
    (net (code "47") (name "VCC") (class "Default")
      (node (ref "C10") (pin "2") (pinfunction "2_2") (pintype "unspecified"))
      (node (ref "C11") (pin "2") (pinfunction "2_2") (pintype "unspecified"))
      (node (ref "C12") (pin "2") (pinfunction "2_2") (pintype "unspecified"))
      (node (ref "C13") (pin "2") (pinfunction "2_2") (pintype "unspecified"))
      (node (ref "C14") (pin "2") (pinfunction "2_2") (pintype "unspecified"))
      (node (ref "C15") (pin "2") (pinfunction "2_2") (pintype "unspecified"))
      (node (ref "C16") (pin "2") (pinfunction "2_2") (pintype "unspecified"))
      (node (ref "C17") (pin "1") (pinfunction "1_1") (pintype "input"))
      (node (ref "C21") (pin "2") (pinfunction "2_2") (pintype "unspecified"))
      (node (ref "C22") (pin "2") (pinfunction "2_2") (pintype "unspecified"))
      (node (ref "C23") (pin "2") (pinfunction "2_2") (pintype "unspecified"))
      (node (ref "C3") (pin "2") (pinfunction "2_2") (pintype "unspecified"))
      (node (ref "C31") (pin "2") (pinfunction "2_2") (pintype "unspecified"))
      (node (ref "C4") (pin "2") (pinfunction "2_2") (pintype "unspecified"))
      (node (ref "C6") (pin "2") (pinfunction "2_2") (pintype "unspecified"))
      (node (ref "C7") (pin "2") (pinfunction "2_2") (pintype "unspecified"))
      (node (ref "C9") (pin "2") (pinfunction "2_2") (pintype "unspecified"))
      (node (ref "Q1") (pin "5") (pinfunction "D_5") (pintype "unspecified"))
      (node (ref "Q3") (pin "5") (pinfunction "D_5") (pintype "unspecified"))
      (node (ref "Q5") (pin "5") (pinfunction "D_5") (pintype "unspecified"))
      (node (ref "U1") (pin "1") (pinfunction "GVDD_1") (pintype "unspecified"))
      (node (ref "U2") (pin "1") (pinfunction "GVDD_1") (pintype "unspecified"))
      (node (ref "U3") (pin "1") (pinfunction "GVDD_1") (pintype "unspecified"))
      (node (ref "U7") (pin "1") (pinfunction "VIN_1") (pintype "unspecified"))
      (node (ref "U8") (pin "1") (pinfunction "VIN_1") (pintype "unspecified"))
      (node (ref "power") (pin "2") (pinfunction "+_2") (pintype "input"))
    )
    (net (code "48") (name "unconnected-(SCREW1-Pad1)") (class "Default")
      (node (ref "SCREW1") (pin "1") (pinfunction "1_1") (pintype "input"))
    )
    (net (code "49") (name "unconnected-(SCREW2-Pad1)") (class "Default")
      (node (ref "SCREW2") (pin "1") (pinfunction "1_1") (pintype "input"))
    )
    (net (code "50") (name "unconnected-(SCREW3-Pad1)") (class "Default")
      (node (ref "SCREW3") (pin "1") (pinfunction "1_1") (pintype "input"))
    )
    (net (code "51") (name "unconnected-(SCREW4-Pad1)") (class "Default")
      (node (ref "SCREW4") (pin "1") (pinfunction "1_1") (pintype "input"))
    )
    (net (code "52") (name "unconnected-(U4-PA0-Pad7)") (class "Default")
      (node (ref "U4") (pin "7") (pinfunction "PA0_7") (pintype "unspecified"))
    )
    (net (code "53") (name "unconnected-(U4-PA1-Pad8)") (class "Default")
      (node (ref "U4") (pin "8") (pinfunction "PA1_8") (pintype "unspecified"))
    )
    (net (code "54") (name "unconnected-(U4-PA11[PA9]-Pad22)") (class "Default")
      (node (ref "U4") (pin "22") (pinfunction "PA11[PA9]_22") (pintype "unspecified"))
    )
    (net (code "55") (name "unconnected-(U4-PA12[PA10]-Pad23)") (class "Default")
      (node (ref "U4") (pin "23") (pinfunction "PA12[PA10]_23") (pintype "unspecified"))
    )
    (net (code "56") (name "unconnected-(U4-PA15-Pad26)") (class "Default")
      (node (ref "U4") (pin "26") (pinfunction "PA15_26") (pintype "unspecified"))
    )
    (net (code "57") (name "unconnected-(U4-PB2-Pad17)") (class "Default")
      (node (ref "U4") (pin "17") (pinfunction "PB2_17") (pintype "unspecified"))
    )
    (net (code "58") (name "unconnected-(U4-PB9-Pad1)") (class "Default")
      (node (ref "U4") (pin "1") (pinfunction "PB9_1") (pintype "unspecified"))
    )
    (net (code "59") (name "unconnected-(U4-PC6-Pad20)") (class "Default")
      (node (ref "U4") (pin "20") (pinfunction "PC6_20") (pintype "unspecified"))
    )
    (net (code "60") (name "unconnected-(U4-PC14-OSC32IN-Pad2)") (class "Default")
      (node (ref "U4") (pin "2") (pinfunction "PC14-OSC32IN_2") (pintype "unspecified"))
    )
    (net (code "61") (name "unconnected-(U4-PC15-OSC32OUT-Pad3)") (class "Default")
      (node (ref "U4") (pin "3") (pinfunction "PC15-OSC32OUT_3") (pintype "unspecified"))
    )
  )
)
